# switch_and_PA.net
KiCad netlist of a schematic drawn in Altium Designer
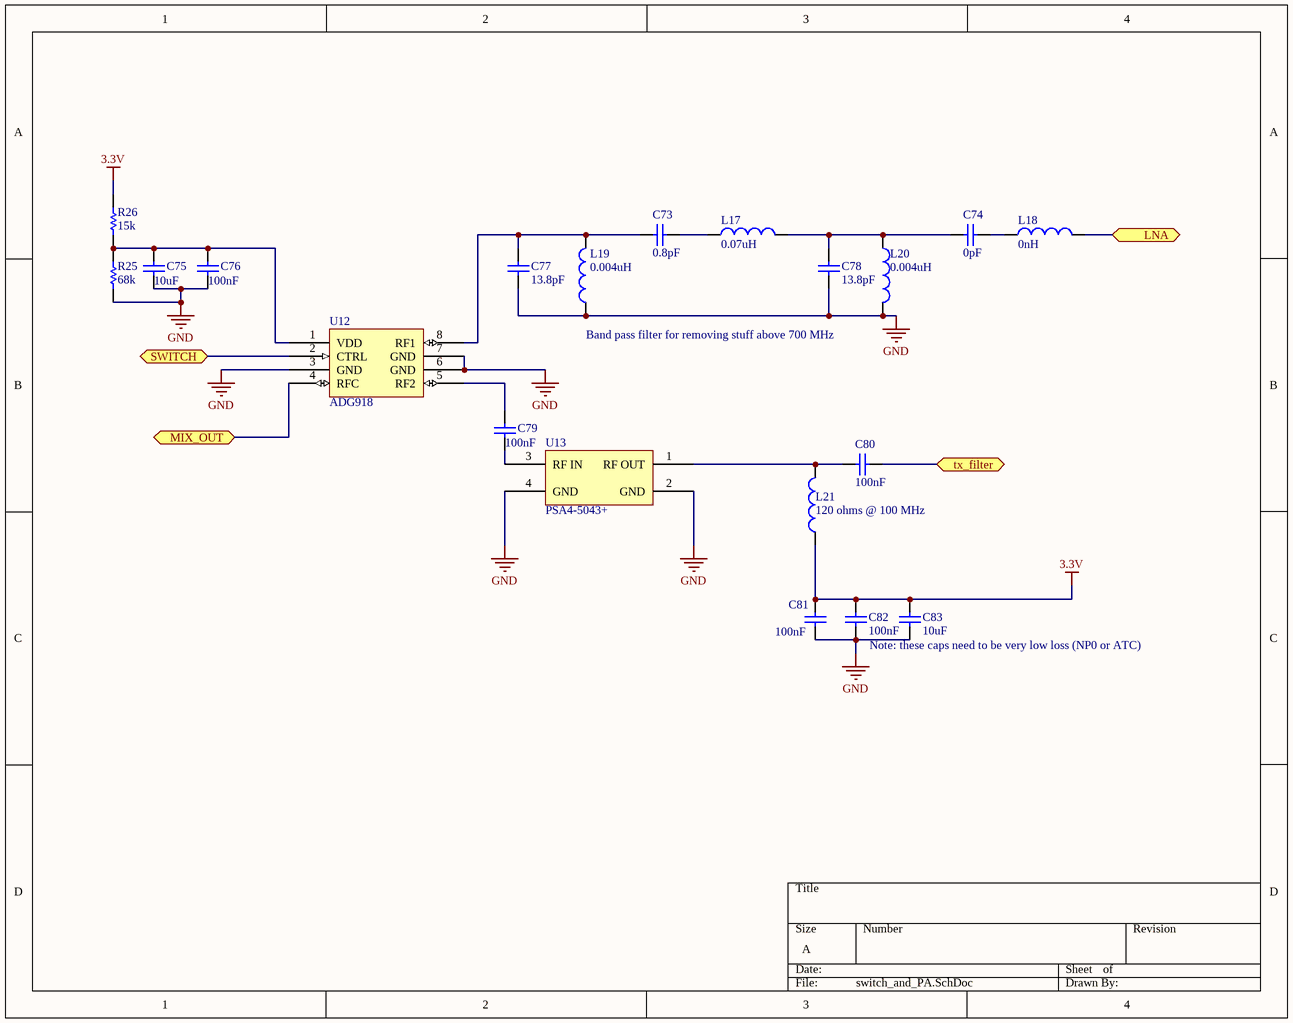
[diagram p0: switch_and_PA.SchDoc]

(export (version "E")
  (design (tool "Eeschema 10.0.6"))
  (components
    (comp (ref "C73")
      (value "0.8pF")
      (footprint "0402")
      (description "Capacitor (Semiconductor SIM Model)")
      (fields (field (name "Comment") "Cap Semi") (field (name "PUBLISHER") "Altium Limited"))
      (libsource (lib "Miscellaneous Devices") (part "Cap Semi"))
    )
    (comp (ref "C74")
      (value "0pF")
      (footprint "0402")
      (description "Capacitor (Semiconductor SIM Model)")
      (fields (field (name "Comment") "Cap Semi") (field (name "PUBLISHER") "Altium Limited"))
      (libsource (lib "Miscellaneous Devices") (part "Cap Semi"))
    )
    (comp (ref "C75")
      (value "10uF")
      (footprint "0402")
      (description "Capacitor (Semiconductor SIM Model)")
      (fields (field (name "Comment") "Cap Semi") (field (name "PUBLISHER") "Altium Limited"))
      (libsource (lib "Miscellaneous Devices") (part "Cap Semi"))
    )
    (comp (ref "C76")
      (value "100nF")
      (footprint "0402")
      (description "Capacitor (Semiconductor SIM Model)")
      (fields (field (name "Comment") "Cap Semi") (field (name "PUBLISHER") "Altium Limited"))
      (libsource (lib "Miscellaneous Devices") (part "Cap Semi"))
    )
    (comp (ref "C77")
      (value "13.8pF")
      (footprint "0402")
      (description "Capacitor (Semiconductor SIM Model)")
      (fields (field (name "Comment") "Cap Semi") (field (name "PUBLISHER") "Altium Limited"))
      (libsource (lib "Miscellaneous Devices") (part "Cap Semi"))
    )
    (comp (ref "C78")
      (value "13.8pF")
      (footprint "0402")
      (description "Capacitor (Semiconductor SIM Model)")
      (fields (field (name "Comment") "Cap Semi") (field (name "PUBLISHER") "Altium Limited"))
      (libsource (lib "Miscellaneous Devices") (part "Cap Semi"))
    )
    (comp (ref "C79")
      (value "100nF")
      (footprint "0402")
      (description "Capacitor (Semiconductor SIM Model)")
      (fields (field (name "Comment") "Cap Semi") (field (name "PUBLISHER") "Altium Limited"))
      (libsource (lib "Miscellaneous Devices") (part "Cap Semi"))
    )
    (comp (ref "C80")
      (value "100nF")
      (footprint "0402")
      (description "Capacitor (Semiconductor SIM Model)")
      (fields (field (name "Comment") "Cap Semi") (field (name "PUBLISHER") "Altium Limited"))
      (libsource (lib "Miscellaneous Devices") (part "Cap Semi"))
    )
    (comp (ref "C81")
      (value "100nF")
      (footprint "0402")
      (description "Capacitor (Semiconductor SIM Model)")
      (fields (field (name "Comment") "Cap Semi") (field (name "PUBLISHER") "Altium Limited"))
      (libsource (lib "Miscellaneous Devices") (part "Cap Semi"))
    )
    (comp (ref "C82")
      (value "100nF")
      (footprint "0402")
      (description "Capacitor (Semiconductor SIM Model)")
      (fields (field (name "Comment") "Cap Semi") (field (name "PUBLISHER") "Altium Limited"))
      (libsource (lib "Miscellaneous Devices") (part "Cap Semi"))
    )
    (comp (ref "C83")
      (value "10uF")
      (footprint "0402")
      (description "Capacitor (Semiconductor SIM Model)")
      (fields (field (name "Comment") "Cap Semi") (field (name "PUBLISHER") "Altium Limited"))
      (libsource (lib "Miscellaneous Devices") (part "Cap Semi"))
    )
    (comp (ref "L17")
      (value "0.07uH")
      (footprint "0402")
      (description "Inductor")
      (fields (field (name "PUBLISHER") "Altium Limited"))
      (libsource (lib "Miscellaneous Devices") (part "Inductor"))
    )
    (comp (ref "L18")
      (value "0nH")
      (footprint "0402")
      (description "Inductor")
      (fields (field (name "PUBLISHER") "Altium Limited"))
      (libsource (lib "Miscellaneous Devices") (part "Inductor"))
    )
    (comp (ref "L19")
      (value "0.004uH")
      (footprint "0402")
      (description "Inductor")
      (fields (field (name "PUBLISHER") "Altium Limited"))
      (libsource (lib "Miscellaneous Devices") (part "Inductor"))
    )
    (comp (ref "L20")
      (value "0.004uH")
      (footprint "0402")
      (description "Inductor")
      (fields (field (name "PUBLISHER") "Altium Limited"))
      (libsource (lib "Miscellaneous Devices") (part "Inductor"))
    )
    (comp (ref "L21")
      (value "120 ohms @ 100 MHz")
      (footprint "0402")
      (description "Inductor")
      (fields (field (name "PUBLISHER") "Altium Limited"))
      (libsource (lib "Miscellaneous Devices") (part "Inductor"))
    )
    (comp (ref "R25")
      (value "68k")
      (footprint "0402")
      (description "Semiconductor Resistor")
      (fields (field (name "Comment") "Res Semi") (field (name "PUBLISHER") "Altium Limited"))
      (libsource (lib "Miscellaneous Devices") (part "Res Semi"))
    )
    (comp (ref "R26")
      (value "15k")
      (footprint "0402")
      (description "Semiconductor Resistor")
      (fields (field (name "Comment") "Res Semi") (field (name "PUBLISHER") "Altium Limited"))
      (libsource (lib "Miscellaneous Devices") (part "Res Semi"))
    )
    (comp (ref "U12")
      (value "ADG918")
      (footprint "ADG918")
      (description "RF Switch")
      (fields
        (field (name "MANUFACTURER") "Analog Devices Inc")
        (field (name "MANUFACTURER PART NUMBER") "ADG918BRMZ")
      )
      (libsource (lib "Parts") (part "ADG918"))
    )
    (comp (ref "U13")
      (value "PSA4-5043+")
      (description "LNA")
      (libsource (lib "shield_components") (part "PSA4-5043+"))
    )
  )
  (nets
    (net (code "1") (name "/LNA") (class "Default")
      (node (ref "L18") (pin "2") (pinfunction "2_2") (pintype "passive"))
    )
    (net (code "2") (name "/MIX_OUT") (class "Default")
      (node (ref "U12") (pin "4") (pinfunction "RFC_4") (pintype "bidirectional"))
    )
    (net (code "3") (name "/SWITCH") (class "Default")
      (node (ref "U12") (pin "2") (pinfunction "CTRL_2") (pintype "input"))
    )
    (net (code "4") (name "/tx_filter") (class "Default")
      (node (ref "C80") (pin "1") (pinfunction "1_1") (pintype "passive"))
    )
    (net (code "5") (name "3.3V") (class "Default")
      (node (ref "C81") (pin "1") (pinfunction "1_1") (pintype "passive"))
      (node (ref "C82") (pin "1") (pinfunction "1_1") (pintype "passive"))
      (node (ref "C83") (pin "1") (pinfunction "1_1") (pintype "passive"))
      (node (ref "L21") (pin "1") (pinfunction "1_1") (pintype "passive"))
      (node (ref "R26") (pin "1") (pinfunction "1_1") (pintype "passive"))
    )
    (net (code "6") (name "GND") (class "Default")
      (node (ref "C75") (pin "1") (pinfunction "1_1") (pintype "passive"))
      (node (ref "C76") (pin "1") (pinfunction "1_1") (pintype "passive"))
      (node (ref "C77") (pin "2") (pinfunction "2_2") (pintype "passive"))
      (node (ref "C78") (pin "2") (pinfunction "2_2") (pintype "passive"))
      (node (ref "C81") (pin "2") (pinfunction "2_2") (pintype "passive"))
      (node (ref "C82") (pin "2") (pinfunction "2_2") (pintype "passive"))
      (node (ref "C83") (pin "2") (pinfunction "2_2") (pintype "passive"))
      (node (ref "L19") (pin "1") (pinfunction "1_1") (pintype "passive"))
      (node (ref "L20") (pin "2") (pinfunction "2_2") (pintype "passive"))
      (node (ref "R25") (pin "2") (pinfunction "2_2") (pintype "passive"))
      (node (ref "U12") (pin "3") (pinfunction "GND_3") (pintype "power_in"))
      (node (ref "U12") (pin "6") (pinfunction "GND_6") (pintype "power_in"))
      (node (ref "U12") (pin "7") (pinfunction "GND_7") (pintype "power_in"))
      (node (ref "U13") (pin "2") (pinfunction "GND_2") (pintype "passive"))
      (node (ref "U13") (pin "4") (pinfunction "GND_4") (pintype "passive"))
    )
    (net (code "7") (name "Net-(C73-Pad1)") (class "Default")
      (node (ref "C73") (pin "1") (pinfunction "1_1") (pintype "passive"))
      (node (ref "L17") (pin "1") (pinfunction "1_1") (pintype "passive"))
    )
    (net (code "8") (name "Net-(C74-Pad1)") (class "Default")
      (node (ref "C74") (pin "1") (pinfunction "1_1") (pintype "passive"))
      (node (ref "L18") (pin "1") (pinfunction "1_1") (pintype "passive"))
    )
    (net (code "9") (name "Net-(C74-Pad2)") (class "Default")
      (node (ref "C74") (pin "2") (pinfunction "2_2") (pintype "passive"))
      (node (ref "C78") (pin "1") (pinfunction "1_1") (pintype "passive"))
      (node (ref "L17") (pin "2") (pinfunction "2_2") (pintype "passive"))
      (node (ref "L20") (pin "1") (pinfunction "1_1") (pintype "passive"))
    )
    (net (code "10") (name "Net-(U12-RF1)") (class "Default")
      (node (ref "C73") (pin "2") (pinfunction "2_2") (pintype "passive"))
      (node (ref "C77") (pin "1") (pinfunction "1_1") (pintype "passive"))
      (node (ref "L19") (pin "2") (pinfunction "2_2") (pintype "passive"))
      (node (ref "U12") (pin "8") (pinfunction "RF1_8") (pintype "bidirectional"))
    )
    (net (code "11") (name "Net-(U12-RF2)") (class "Default")
      (node (ref "C79") (pin "2") (pinfunction "2_2") (pintype "passive"))
      (node (ref "U12") (pin "5") (pinfunction "RF2_5") (pintype "bidirectional"))
    )
    (net (code "12") (name "Net-(U12-VDD)") (class "Default")
      (node (ref "C75") (pin "2") (pinfunction "2_2") (pintype "passive"))
      (node (ref "C76") (pin "2") (pinfunction "2_2") (pintype "passive"))
      (node (ref "R25") (pin "1") (pinfunction "1_1") (pintype "passive"))
      (node (ref "R26") (pin "2") (pinfunction "2_2") (pintype "passive"))
      (node (ref "U12") (pin "1") (pinfunction "VDD_1") (pintype "power_in"))
    )
    (net (code "13") (name "Net-(U13-RF_IN)") (class "Default")
      (node (ref "C79") (pin "1") (pinfunction "1_1") (pintype "passive"))
      (node (ref "U13") (pin "3") (pinfunction "RF_IN_3") (pintype "passive"))
    )
    (net (code "14") (name "Net-(U13-RF_OUT)") (class "Default")
      (node (ref "C80") (pin "2") (pinfunction "2_2") (pintype "passive"))
      (node (ref "L21") (pin "2") (pinfunction "2_2") (pintype "passive"))
      (node (ref "U13") (pin "1") (pinfunction "RF_OUT_1") (pintype "passive"))
    )
  )
)
